# RFM95.net
KiCad netlist of a schematic drawn in Altium Designer
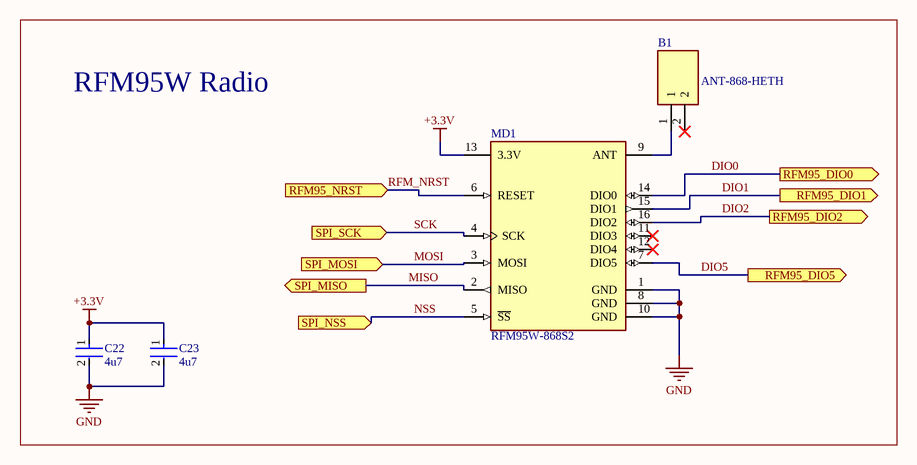
[diagram p0: RFM95.SchDoc]

(export (version "E")
  (design (tool "Eeschema 10.0.6"))
  (components
    (comp (ref "B1")
      (value "ANT-868-HETH")
      (footprint "ANT-868-HETH-Footprint-1")
      (description "RF/Microwave Antenna")
      (libsource (lib "tutorial_PCB") (part "ANT-868-HETH-Symbol-1"))
    )
    (comp (ref "C22")
      (value "4u7")
      (footprint "FP-GRM21B-0_15-MFG")
      (description "Chip Multilayer Ceramic Capacitors for General Purpose, 0805, 4.7uF, X7R, 15%, 10%, 10V")
      (fields (field (name "TOLERANCE") "10%"))
      (libsource (lib "Altium Content Vault") (part "b4654b650e69147ec39a6b967a45e02"))
    )
    (comp (ref "C23")
      (value "4u7")
      (footprint "FP-GRM21B-0_15-MFG")
      (description "Chip Multilayer Ceramic Capacitors for General Purpose, 0805, 4.7uF, X7R, 15%, 10%, 10V")
      (fields (field (name "TOLERANCE") "10%"))
      (libsource (lib "Altium Content Vault") (part "b4654b650e69147ec39a6b967a45e02"))
    )
    (comp (ref "MD1")
      (value "RFM95W-868S2")
      (footprint "FP-RFM95W-868S2-MFG")
      (description "RX TXRX MODULE ISM < 1GHZ SMD")
      (libsource (lib "Altium Content Vault") (part "17626aa6fba47fab2b206b7c140802e"))
    )
  )
  (nets
    (net (code "1") (name "+3.3V") (class "Default")
      (node (ref "C22") (pin "1") (pinfunction "1_1") (pintype "passive"))
      (node (ref "C23") (pin "1") (pinfunction "1_1") (pintype "passive"))
      (node (ref "MD1") (pin "13") (pinfunction "3.3V_13") (pintype "power_in"))
    )
    (net (code "2") (name "/DIO0") (class "Default")
      (node (ref "MD1") (pin "14") (pinfunction "DIO0_14") (pintype "bidirectional"))
    )
    (net (code "3") (name "/DIO1") (class "Default")
      (node (ref "MD1") (pin "15") (pinfunction "DIO1_15") (pintype "output"))
    )
    (net (code "4") (name "/DIO2") (class "Default")
      (node (ref "MD1") (pin "16") (pinfunction "DIO2_16") (pintype "bidirectional"))
    )
    (net (code "5") (name "/DIO5") (class "Default")
      (node (ref "MD1") (pin "7") (pinfunction "DIO5_7") (pintype "bidirectional"))
    )
    (net (code "6") (name "/MISO") (class "Default")
      (node (ref "MD1") (pin "2") (pinfunction "MISO_2") (pintype "output"))
    )
    (net (code "7") (name "/MOSI") (class "Default")
      (node (ref "MD1") (pin "3") (pinfunction "MOSI_3") (pintype "input"))
    )
    (net (code "8") (name "/NSS") (class "Default")
      (node (ref "MD1") (pin "5") (pinfunction "~{SS}_5") (pintype "input"))
    )
    (net (code "9") (name "/RFM_NRST") (class "Default")
      (node (ref "MD1") (pin "6") (pinfunction "RESET_6") (pintype "input"))
    )
    (net (code "10") (name "/SCK") (class "Default")
      (node (ref "MD1") (pin "4") (pinfunction "SCK_4") (pintype "input"))
    )
    (net (code "11") (name "GND") (class "Default")
      (node (ref "C22") (pin "2") (pinfunction "2_2") (pintype "passive"))
      (node (ref "C23") (pin "2") (pinfunction "2_2") (pintype "passive"))
      (node (ref "MD1") (pin "1") (pinfunction "GND_1") (pintype "power_in"))
      (node (ref "MD1") (pin "10") (pinfunction "GND_10") (pintype "power_in"))
      (node (ref "MD1") (pin "8") (pinfunction "GND_8") (pintype "power_in"))
    )
    (net (code "12") (name "Net-(MD1-ANT)") (class "Default")
      (node (ref "B1") (pin "1") (pinfunction "1_1") (pintype "passive"))
      (node (ref "MD1") (pin "9") (pinfunction "ANT_9") (pintype "passive"))
    )
    (net (code "13") (name "unconnected-(B1-Pad2)") (class "Default")
      (node (ref "B1") (pin "2") (pinfunction "2_2") (pintype "passive+no_connect"))
    )
    (net (code "14") (name "unconnected-(MD1-DIO3-Pad11)") (class "Default")
      (node (ref "MD1") (pin "11") (pinfunction "DIO3_11") (pintype "bidirectional+no_connect"))
    )
    (net (code "15") (name "unconnected-(MD1-DIO4-Pad12)") (class "Default")
      (node (ref "MD1") (pin "12") (pinfunction "DIO4_12") (pintype "bidirectional+no_connect"))
    )
  )
)
